# Analog.net
KiCad netlist of a schematic drawn in Altium Designer
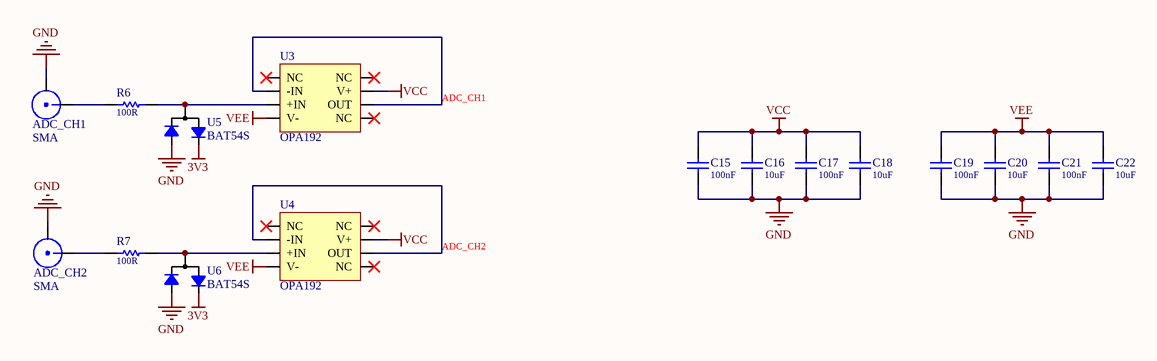
[diagram p0: Analog.SchDoc]

(export (version "E")
  (design (tool "Eeschema 10.0.6"))
  (components
    (comp (ref "ADC_CH1") (value "SMA") (footprint "SMA1") (libsource (lib "XuZhe") (part "SMA")))
    (comp (ref "ADC_CH2") (value "SMA") (footprint "SMA1") (libsource (lib "XuZhe") (part "SMA")))
    (comp (ref "C15")
      (value "100nF")
      (footprint "C0603-L")
      (description "贴片瓷片电容")
      (fields (field (name "Comment") "Cap-S"))
      (libsource (lib "XuZhe") (part "Cap-S"))
    )
    (comp (ref "C16")
      (value "10uF")
      (footprint "C0603-L")
      (description "贴片瓷片电容")
      (fields (field (name "Comment") "Cap-S"))
      (libsource (lib "XuZhe") (part "Cap-S"))
    )
    (comp (ref "C17")
      (value "100nF")
      (footprint "C0603-L")
      (description "贴片瓷片电容")
      (fields (field (name "Comment") "Cap-S"))
      (libsource (lib "XuZhe") (part "Cap-S"))
    )
    (comp (ref "C18")
      (value "10uF")
      (footprint "C0603-L")
      (description "贴片瓷片电容")
      (fields (field (name "Comment") "Cap-S"))
      (libsource (lib "XuZhe") (part "Cap-S"))
    )
    (comp (ref "C19")
      (value "100nF")
      (footprint "C0603-L")
      (description "贴片瓷片电容")
      (fields (field (name "Comment") "Cap-S"))
      (libsource (lib "XuZhe") (part "Cap-S"))
    )
    (comp (ref "C20")
      (value "10uF")
      (footprint "C0603-L")
      (description "贴片瓷片电容")
      (fields (field (name "Comment") "Cap-S"))
      (libsource (lib "XuZhe") (part "Cap-S"))
    )
    (comp (ref "C21")
      (value "100nF")
      (footprint "C0603-L")
      (description "贴片瓷片电容")
      (fields (field (name "Comment") "Cap-S"))
      (libsource (lib "XuZhe") (part "Cap-S"))
    )
    (comp (ref "C22")
      (value "10uF")
      (footprint "C0603-L")
      (description "贴片瓷片电容")
      (fields (field (name "Comment") "Cap-S"))
      (libsource (lib "XuZhe") (part "Cap-S"))
    )
    (comp (ref "R6")
      (value "100R")
      (footprint "R0603-L")
      (description "贴片电阻")
      (fields (field (name "Comment") "R"))
      (libsource (lib "XuZhe") (part "Res"))
    )
    (comp (ref "R7")
      (value "100R")
      (footprint "R0603-L")
      (description "贴片电阻")
      (fields (field (name "Comment") "R"))
      (libsource (lib "XuZhe") (part "Res"))
    )
    (comp (ref "U3")
      (value "OPA192")
      (footprint "SOIC127P600X175-8N")
      (libsource (lib "OPA192") (part "OPA192"))
    )
    (comp (ref "U4")
      (value "OPA192")
      (footprint "SOIC127P600X175-8N")
      (libsource (lib "OPA192") (part "OPA192"))
    )
    (comp (ref "U5") (value "BAT54S") (footprint "SOT-23-3") (libsource (lib "XuZhe") (part "BAT54S")))
    (comp (ref "U6") (value "BAT54S") (footprint "SOT-23-3") (libsource (lib "XuZhe") (part "BAT54S")))
  )
  (nets
    (net (code "1") (name "/ADC_CH1") (class "Default")
      (node (ref "U3") (pin "2") (pinfunction "-IN_2") (pintype "passive"))
      (node (ref "U3") (pin "6") (pinfunction "OUT_6") (pintype "passive"))
    )
    (net (code "2") (name "/ADC_CH2") (class "Default")
      (node (ref "U4") (pin "2") (pinfunction "-IN_2") (pintype "passive"))
      (node (ref "U4") (pin "6") (pinfunction "OUT_6") (pintype "passive"))
    )
    (net (code "3") (name "3V3") (class "Default")
      (node (ref "U5") (pin "3") (pinfunction "3_3") (pintype "passive"))
      (node (ref "U6") (pin "3") (pinfunction "3_3") (pintype "passive"))
    )
    (net (code "4") (name "GND") (class "Default")
      (node (ref "ADC_CH1") (pin "2") (pinfunction "2_2") (pintype "passive"))
      (node (ref "ADC_CH2") (pin "2") (pinfunction "2_2") (pintype "passive"))
      (node (ref "C15") (pin "1") (pinfunction "1_1") (pintype "passive"))
      (node (ref "C16") (pin "1") (pinfunction "1_1") (pintype "passive"))
      (node (ref "C17") (pin "1") (pinfunction "1_1") (pintype "passive"))
      (node (ref "C18") (pin "1") (pinfunction "1_1") (pintype "passive"))
      (node (ref "C19") (pin "1") (pinfunction "1_1") (pintype "passive"))
      (node (ref "C20") (pin "1") (pinfunction "1_1") (pintype "passive"))
      (node (ref "C21") (pin "1") (pinfunction "1_1") (pintype "passive"))
      (node (ref "C22") (pin "1") (pinfunction "1_1") (pintype "passive"))
      (node (ref "U5") (pin "1") (pinfunction "1_1") (pintype "passive"))
      (node (ref "U6") (pin "1") (pinfunction "1_1") (pintype "passive"))
    )
    (net (code "5") (name "Net-(ADC_CH1-Pad1)") (class "Default")
      (node (ref "ADC_CH1") (pin "1") (pinfunction "1_1") (pintype "passive"))
      (node (ref "R6") (pin "1") (pinfunction "1_1") (pintype "passive"))
    )
    (net (code "6") (name "Net-(ADC_CH2-Pad1)") (class "Default")
      (node (ref "ADC_CH2") (pin "1") (pinfunction "1_1") (pintype "passive"))
      (node (ref "R7") (pin "1") (pinfunction "1_1") (pintype "passive"))
    )
    (net (code "7") (name "Net-(U3-+IN)") (class "Default")
      (node (ref "R6") (pin "2") (pinfunction "2_2") (pintype "passive"))
      (node (ref "U3") (pin "3") (pinfunction "+IN_3") (pintype "passive"))
      (node (ref "U5") (pin "2") (pinfunction "2_2") (pintype "passive"))
    )
    (net (code "8") (name "Net-(U4-+IN)") (class "Default")
      (node (ref "R7") (pin "2") (pinfunction "2_2") (pintype "passive"))
      (node (ref "U4") (pin "3") (pinfunction "+IN_3") (pintype "passive"))
      (node (ref "U6") (pin "2") (pinfunction "2_2") (pintype "passive"))
    )
    (net (code "9") (name "VCC") (class "Default")
      (node (ref "C15") (pin "2") (pinfunction "2_2") (pintype "passive"))
      (node (ref "C16") (pin "2") (pinfunction "2_2") (pintype "passive"))
      (node (ref "C17") (pin "2") (pinfunction "2_2") (pintype "passive"))
      (node (ref "C18") (pin "2") (pinfunction "2_2") (pintype "passive"))
      (node (ref "U3") (pin "7") (pinfunction "V+_7") (pintype "passive"))
      (node (ref "U4") (pin "7") (pinfunction "V+_7") (pintype "passive"))
    )
    (net (code "10") (name "VEE") (class "Default")
      (node (ref "C19") (pin "2") (pinfunction "2_2") (pintype "passive"))
      (node (ref "C20") (pin "2") (pinfunction "2_2") (pintype "passive"))
      (node (ref "C21") (pin "2") (pinfunction "2_2") (pintype "passive"))
      (node (ref "C22") (pin "2") (pinfunction "2_2") (pintype "passive"))
      (node (ref "U3") (pin "4") (pinfunction "V-_4") (pintype "passive"))
      (node (ref "U4") (pin "4") (pinfunction "V-_4") (pintype "passive"))
    )
    (net (code "11") (name "unconnected-(U3-NC-Pad1)") (class "Default")
      (node (ref "U3") (pin "1") (pinfunction "NC_1") (pintype "passive+no_connect"))
    )
    (net (code "12") (name "unconnected-(U3-NC-Pad5)") (class "Default")
      (node (ref "U3") (pin "5") (pinfunction "NC_5") (pintype "passive+no_connect"))
    )
    (net (code "13") (name "unconnected-(U3-NC-Pad8)") (class "Default")
      (node (ref "U3") (pin "8") (pinfunction "NC_8") (pintype "passive+no_connect"))
    )
    (net (code "14") (name "unconnected-(U4-NC-Pad1)") (class "Default")
      (node (ref "U4") (pin "1") (pinfunction "NC_1") (pintype "passive+no_connect"))
    )
    (net (code "15") (name "unconnected-(U4-NC-Pad5)") (class "Default")
      (node (ref "U4") (pin "5") (pinfunction "NC_5") (pintype "passive+no_connect"))
    )
    (net (code "16") (name "unconnected-(U4-NC-Pad8)") (class "Default")
      (node (ref "U4") (pin "8") (pinfunction "NC_8") (pintype "passive+no_connect"))
    )
  )
)
